# SCH_flowMeasurement_2025-10-13.net
KiCad netlist of a schematic drawn in EasyEDA
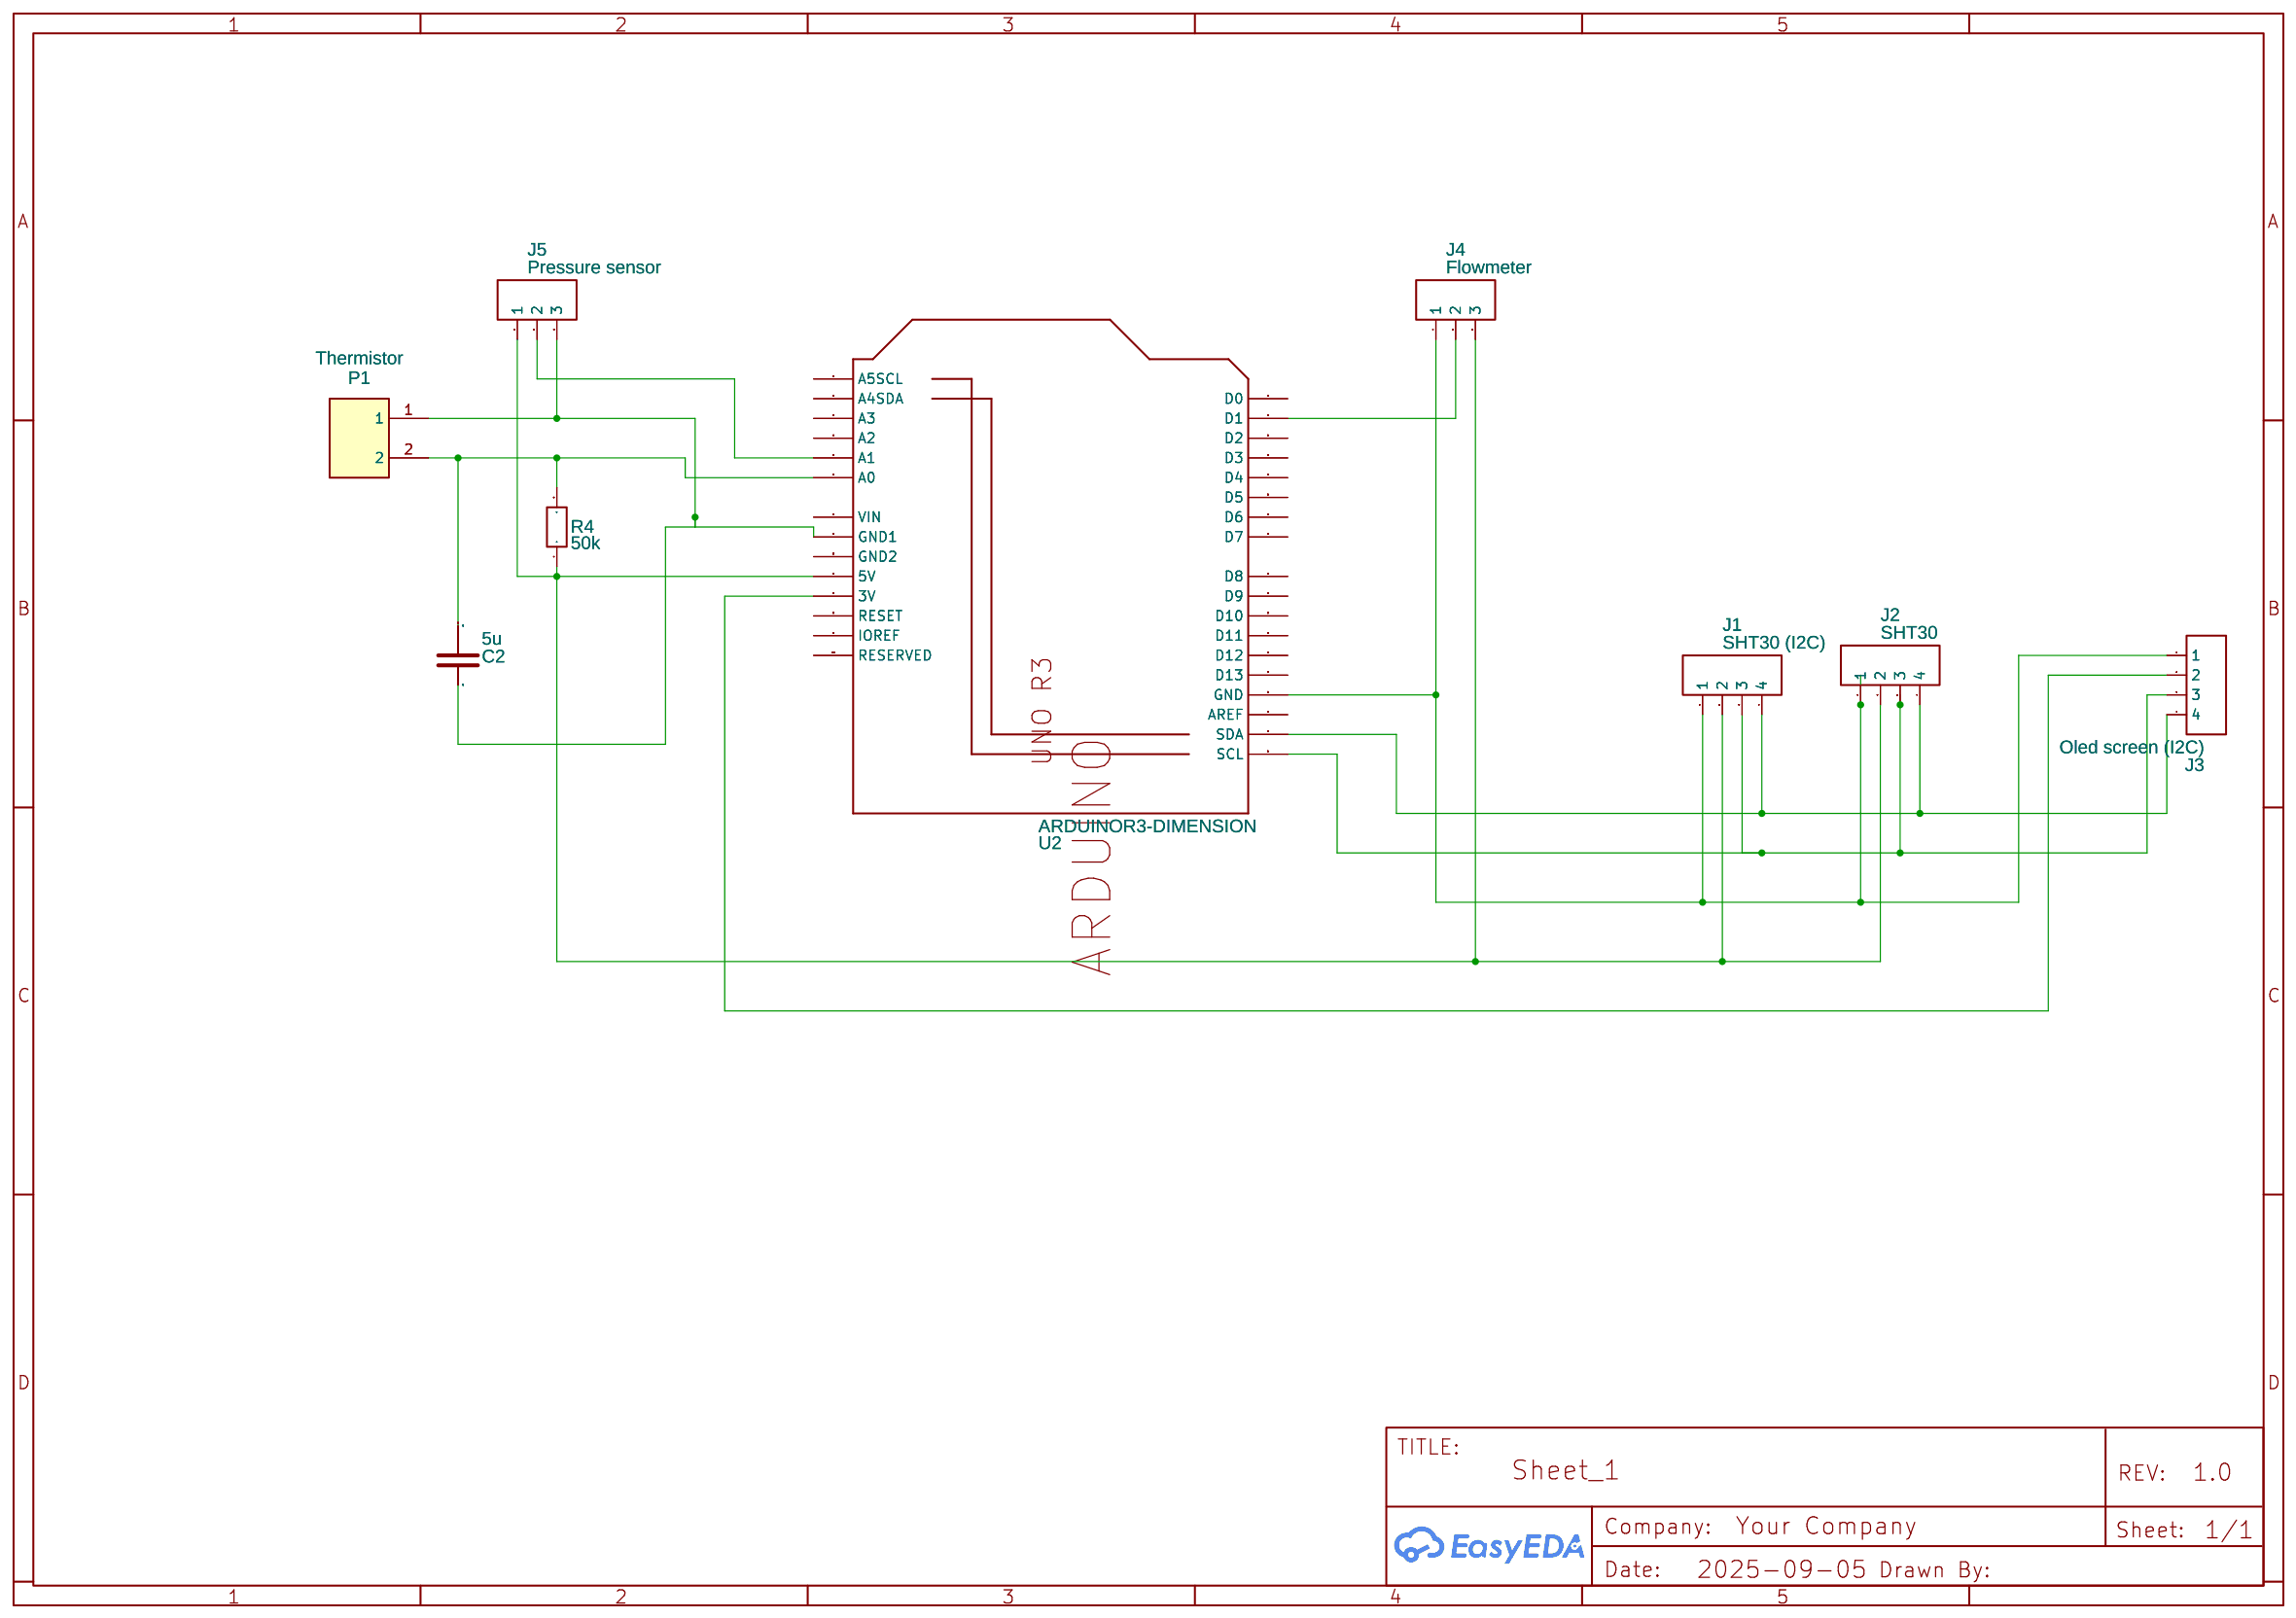
[diagram p0: schematic sheet]

(export (version "E")
  (design (tool "Eeschema 10.0.6"))
  (components
    (comp (ref "C2") (value "5u") (libsource (lib "") (part "CAPACITOR")))
    (comp (ref "J1") (value "SHT30 (I2C)") (libsource (lib "") (part "HDR-M-2.54_1x4")))
    (comp (ref "J2") (value "SHT30") (libsource (lib "") (part "HDR-M-2.54_1x4")))
    (comp (ref "J3") (value "Oled screen (I2C)") (libsource (lib "") (part "HDR-M-2.54_1x4_1")))
    (comp (ref "J4") (value "Flowmeter") (libsource (lib "") (part "HDR-M-2.54_1x3")))
    (comp (ref "J5") (value "Pressure sensor") (libsource (lib "") (part "HDR-M-2.54_1x3")))
    (comp (ref "P1")
      (value "Thermistor")
      (fields (field (name "Manufacturer Part") "PH-2A") (field (name "Manufacturer") "BOOMELE(博穆精密)"))
      (libsource (lib "") (part "PH-2A_C2319"))
    )
    (comp (ref "R4") (value "50k") (libsource (lib "") (part "R_AXIAL-0.4_EU")))
    (comp (ref "U2") (value "ARDUINOR3-DIMENSION") (libsource (lib "") (part "ARDUINOR3-DIMENSION")))
  )
  (nets
    (net (code "1") (name "Net-(C2-PadP$1)") (class "Default")
      (node (ref "C2") (pin "P$1") (pinfunction "P$1_P$1") (pintype "unspecified"))
      (node (ref "J5") (pin "3") (pinfunction "3_3") (pintype "input"))
      (node (ref "P1") (pin "1") (pinfunction "1_1") (pintype "input"))
      (node (ref "U2") (pin "GND1") (pinfunction "GND1_GND1") (pintype "passive"))
    )
    (net (code "2") (name "Net-(C2-PadP$2)") (class "Default")
      (node (ref "C2") (pin "P$2") (pinfunction "P$2_P$2") (pintype "unspecified"))
      (node (ref "P1") (pin "2") (pinfunction "2_2") (pintype "input"))
      (node (ref "R4") (pin "2") (pinfunction "2_2") (pintype "unspecified"))
      (node (ref "U2") (pin "A0") (pinfunction "A0_A0") (pintype "unspecified"))
    )
    (net (code "3") (name "Net-(J1-Pad1)") (class "Default")
      (node (ref "J1") (pin "1") (pinfunction "1_1") (pintype "unspecified"))
      (node (ref "J2") (pin "1") (pinfunction "1_1") (pintype "unspecified"))
      (node (ref "J3") (pin "1") (pinfunction "1_1") (pintype "unspecified"))
      (node (ref "J4") (pin "1") (pinfunction "1_1") (pintype "input"))
      (node (ref "U2") (pin "GND") (pinfunction "GND_GND") (pintype "passive"))
    )
    (net (code "4") (name "Net-(J1-Pad2)") (class "Default")
      (node (ref "J1") (pin "2") (pinfunction "2_2") (pintype "unspecified"))
      (node (ref "J2") (pin "2") (pinfunction "2_2") (pintype "unspecified"))
      (node (ref "J4") (pin "3") (pinfunction "3_3") (pintype "input"))
      (node (ref "J5") (pin "1") (pinfunction "1_1") (pintype "input"))
      (node (ref "R4") (pin "1") (pinfunction "1_1") (pintype "unspecified"))
      (node (ref "U2") (pin "5V") (pinfunction "5V_5V") (pintype "passive"))
    )
    (net (code "5") (name "Net-(J1-Pad3)") (class "Default")
      (node (ref "J1") (pin "3") (pinfunction "3_3") (pintype "unspecified"))
      (node (ref "J2") (pin "3") (pinfunction "3_3") (pintype "unspecified"))
      (node (ref "J3") (pin "3") (pinfunction "3_3") (pintype "unspecified"))
      (node (ref "U2") (pin "SCL") (pinfunction "SCL_SCL") (pintype "unspecified"))
    )
    (net (code "6") (name "Net-(J1-Pad4)") (class "Default")
      (node (ref "J1") (pin "4") (pinfunction "4_4") (pintype "unspecified"))
      (node (ref "J2") (pin "4") (pinfunction "4_4") (pintype "unspecified"))
      (node (ref "J3") (pin "4") (pinfunction "4_4") (pintype "unspecified"))
      (node (ref "U2") (pin "SDA") (pinfunction "SDA_SDA") (pintype "unspecified"))
    )
    (net (code "7") (name "Net-(J3-Pad2)") (class "Default")
      (node (ref "J3") (pin "2") (pinfunction "2_2") (pintype "unspecified"))
      (node (ref "U2") (pin "3V") (pinfunction "3V_3V") (pintype "passive"))
    )
    (net (code "8") (name "Net-(J4-Pad2)") (class "Default")
      (node (ref "J4") (pin "2") (pinfunction "2_2") (pintype "input"))
      (node (ref "U2") (pin "D1") (pinfunction "D1_D1") (pintype "unspecified"))
    )
    (net (code "9") (name "Net-(J5-Pad2)") (class "Default")
      (node (ref "J5") (pin "2") (pinfunction "2_2") (pintype "input"))
      (node (ref "U2") (pin "A1") (pinfunction "A1_A1") (pintype "unspecified"))
    )
    (net (code "10") (name "unconnected-(U2-A4SDA-PadA4)") (class "Default")
      (node (ref "U2") (pin "A4") (pinfunction "A4SDA_A4") (pintype "unspecified"))
    )
    (net (code "11") (name "unconnected-(U2-A5SCL-PadA5)") (class "Default")
      (node (ref "U2") (pin "A5") (pinfunction "A5SCL_A5") (pintype "unspecified"))
    )
    (net (code "12") (name "unconnected-(U2-PadA2)") (class "Default")
      (node (ref "U2") (pin "A2") (pinfunction "A2_A2") (pintype "unspecified"))
    )
    (net (code "13") (name "unconnected-(U2-PadA3)") (class "Default")
      (node (ref "U2") (pin "A3") (pinfunction "A3_A3") (pintype "unspecified"))
    )
    (net (code "14") (name "unconnected-(U2-PadAREF)") (class "Default")
      (node (ref "U2") (pin "AREF") (pinfunction "AREF_AREF") (pintype "unspecified"))
    )
    (net (code "15") (name "unconnected-(U2-PadD0)") (class "Default")
      (node (ref "U2") (pin "D0") (pinfunction "D0_D0") (pintype "unspecified"))
    )
    (net (code "16") (name "unconnected-(U2-PadD2)") (class "Default")
      (node (ref "U2") (pin "D2") (pinfunction "D2_D2") (pintype "unspecified"))
    )
    (net (code "17") (name "unconnected-(U2-PadD3)") (class "Default")
      (node (ref "U2") (pin "D3") (pinfunction "D3_D3") (pintype "unspecified"))
    )
    (net (code "18") (name "unconnected-(U2-PadD4)") (class "Default")
      (node (ref "U2") (pin "D4") (pinfunction "D4_D4") (pintype "unspecified"))
    )
    (net (code "19") (name "unconnected-(U2-PadD5)") (class "Default")
      (node (ref "U2") (pin "D5") (pinfunction "D5_D5") (pintype "unspecified"))
    )
    (net (code "20") (name "unconnected-(U2-PadD6)") (class "Default")
      (node (ref "U2") (pin "D6") (pinfunction "D6_D6") (pintype "unspecified"))
    )
    (net (code "21") (name "unconnected-(U2-PadD7)") (class "Default")
      (node (ref "U2") (pin "D7") (pinfunction "D7_D7") (pintype "unspecified"))
    )
    (net (code "22") (name "unconnected-(U2-PadD8)") (class "Default")
      (node (ref "U2") (pin "D8") (pinfunction "D8_D8") (pintype "unspecified"))
    )
    (net (code "23") (name "unconnected-(U2-PadD9)") (class "Default")
      (node (ref "U2") (pin "D9") (pinfunction "D9_D9") (pintype "unspecified"))
    )
    (net (code "24") (name "unconnected-(U2-PadD10)") (class "Default")
      (node (ref "U2") (pin "D10") (pinfunction "D10_D10") (pintype "unspecified"))
    )
    (net (code "25") (name "unconnected-(U2-PadD11)") (class "Default")
      (node (ref "U2") (pin "D11") (pinfunction "D11_D11") (pintype "unspecified"))
    )
    (net (code "26") (name "unconnected-(U2-PadD12)") (class "Default")
      (node (ref "U2") (pin "D12") (pinfunction "D12_D12") (pintype "unspecified"))
    )
    (net (code "27") (name "unconnected-(U2-PadD13)") (class "Default")
      (node (ref "U2") (pin "D13") (pinfunction "D13_D13") (pintype "unspecified"))
    )
    (net (code "28") (name "unconnected-(U2-PadGND2)") (class "Default")
      (node (ref "U2") (pin "GND2") (pinfunction "GND2_GND2") (pintype "passive"))
    )
    (net (code "29") (name "unconnected-(U2-PadIOREF)") (class "Default")
      (node (ref "U2") (pin "IOREF") (pinfunction "IOREF_IOREF") (pintype "output"))
    )
    (net (code "30") (name "unconnected-(U2-PadRESERVED)") (class "Default")
      (node (ref "U2") (pin "RESERVED") (pinfunction "RESERVED_RESERVED") (pintype "unspecified"))
    )
    (net (code "31") (name "unconnected-(U2-PadRESET)") (class "Default")
      (node (ref "U2") (pin "RESET") (pinfunction "RESET_RESET") (pintype "unspecified"))
    )
    (net (code "32") (name "unconnected-(U2-PadVIN)") (class "Default")
      (node (ref "U2") (pin "VIN") (pinfunction "VIN_VIN") (pintype "passive"))
    )
  )
)
